# driver.net
KiCad netlist of a schematic drawn in EAGLE
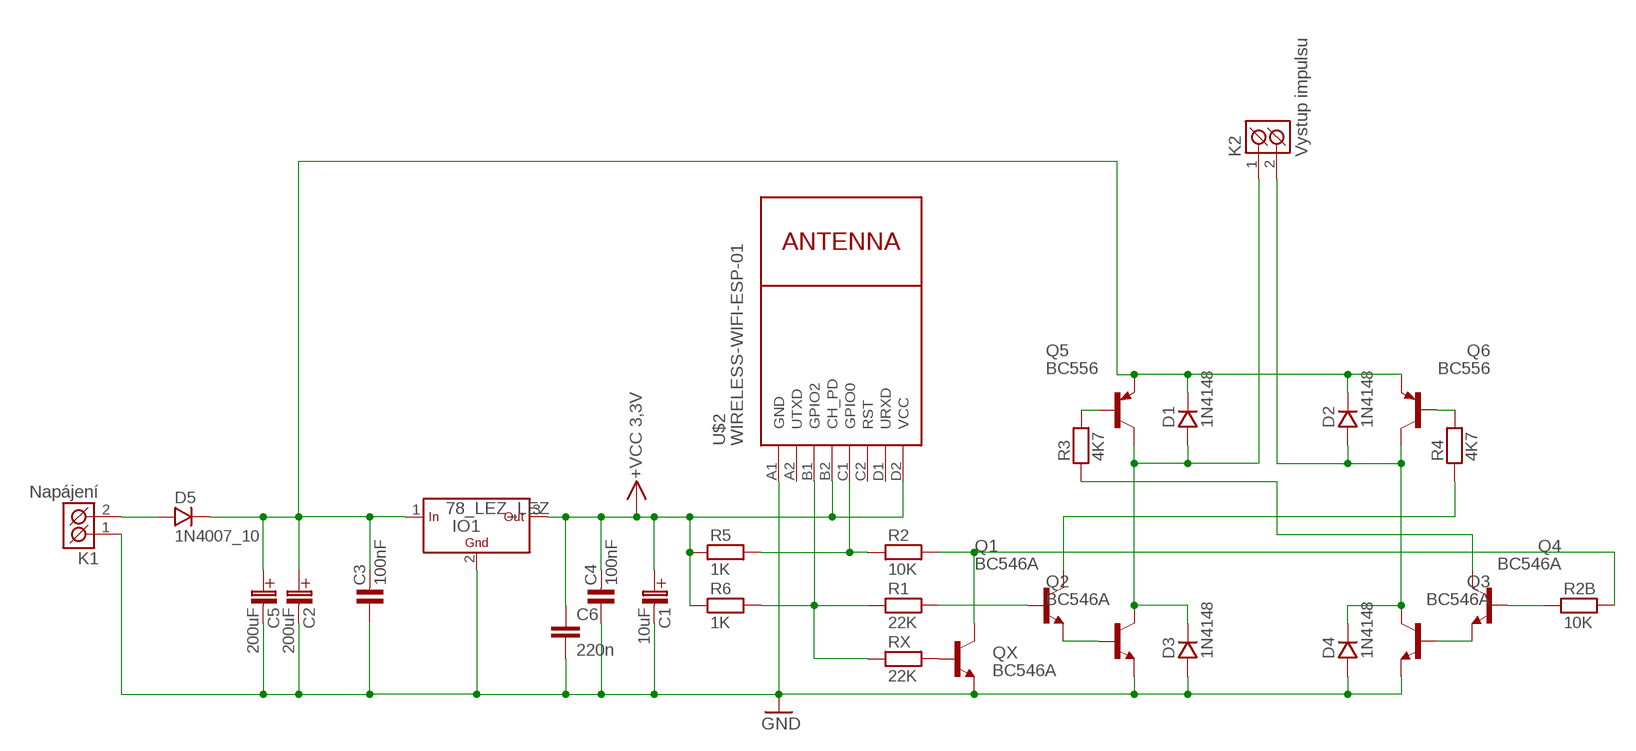
[diagram p0: schematic, sheet 1]

(export (version "E")
  (design (tool "Eeschema 10.0.6"))
  (components
    (comp (ref "C1")
      (value "10uF")
      (footprint "eagle-import:C-EL_2,5")
      (libsource (lib "eagle-import") (part "C-ELEKTROLYT_2,5"))
    )
    (comp (ref "C2")
      (value "200uF")
      (footprint "eagle-import:C-EL_5")
      (libsource (lib "eagle-import") (part "C-ELEKTROLYT_5"))
    )
    (comp (ref "C3")
      (value "100nF")
      (footprint "eagle-import:C-5")
      (libsource (lib "eagle-import") (part "C-KERAMIK_5"))
    )
    (comp (ref "C4")
      (value "100nF")
      (footprint "eagle-import:C-5")
      (libsource (lib "eagle-import") (part "C-KERAMIK_5"))
    )
    (comp (ref "C5")
      (value "200uF")
      (footprint "eagle-import:C-EL_5")
      (libsource (lib "eagle-import") (part "C-ELEKTROLYT_5"))
    )
    (comp (ref "C6")
      (value "220n")
      (footprint "eagle-import:C1206")
      (libsource (lib "eagle-import") (part "C-EUC1206"))
    )
    (comp (ref "D1")
      (value "1N4148")
      (footprint "eagle-import:DO35")
      (libsource (lib "eagle-import") (part "1N4148_7,5"))
    )
    (comp (ref "D2")
      (value "1N4148")
      (footprint "eagle-import:DO35")
      (libsource (lib "eagle-import") (part "1N4148_7,5"))
    )
    (comp (ref "D3")
      (value "1N4148")
      (footprint "eagle-import:DO35")
      (libsource (lib "eagle-import") (part "1N4148_7,5"))
    )
    (comp (ref "D4")
      (value "1N4148")
      (footprint "eagle-import:DO35")
      (libsource (lib "eagle-import") (part "1N4148_7,5"))
    )
    (comp (ref "D5")
      (value "1N4007_10")
      (footprint "eagle-import:DO41")
      (libsource (lib "eagle-import") (part "1N4007_10"))
    )
    (comp (ref "IO1")
      (value "78_LEZ_LEZ")
      (footprint "eagle-import:TO-220")
      (libsource (lib "eagle-import") (part "78??_LEZ"))
    )
    (comp (ref "K1")
      (value "Napájení")
      (footprint "eagle-import:CZM_5_2")
      (libsource (lib "eagle-import") (part "CZM_5/2"))
    )
    (comp (ref "K2")
      (value "Vystup impulsu")
      (footprint "eagle-import:CZM_5_2")
      (libsource (lib "eagle-import") (part "CZM_5/2"))
    )
    (comp (ref "Q1")
      (value "BC546A")
      (footprint "eagle-import:TO92-EBC")
      (libsource (lib "eagle-import") (part "BC546A"))
    )
    (comp (ref "Q2")
      (value "BC546A")
      (footprint "eagle-import:TO92-EBC")
      (libsource (lib "eagle-import") (part "BC546A"))
    )
    (comp (ref "Q3")
      (value "BC546A")
      (footprint "eagle-import:TO92-EBC")
      (libsource (lib "eagle-import") (part "BC546A"))
    )
    (comp (ref "Q4")
      (value "BC546A")
      (footprint "eagle-import:TO92-EBC")
      (libsource (lib "eagle-import") (part "BC546A"))
    )
    (comp (ref "Q5")
      (value "BC556")
      (footprint "eagle-import:TO92-EBC")
      (libsource (lib "eagle-import") (part "BC556"))
    )
    (comp (ref "Q6")
      (value "BC556")
      (footprint "eagle-import:TO92-EBC")
      (libsource (lib "eagle-import") (part "BC556"))
    )
    (comp (ref "QX")
      (value "BC546A")
      (footprint "eagle-import:TO92-EBC")
      (libsource (lib "eagle-import") (part "BC546A"))
    )
    (comp (ref "R1")
      (value "22K")
      (footprint "eagle-import:R-10")
      (libsource (lib "eagle-import") (part "R_10"))
    )
    (comp (ref "R2")
      (value "10K")
      (footprint "eagle-import:R-10")
      (libsource (lib "eagle-import") (part "R_10"))
    )
    (comp (ref "R2B")
      (value "10K")
      (footprint "eagle-import:R-10")
      (libsource (lib "eagle-import") (part "R_10"))
    )
    (comp (ref "R3")
      (value "4K7")
      (footprint "eagle-import:R-10")
      (libsource (lib "eagle-import") (part "R_10"))
    )
    (comp (ref "R4")
      (value "4K7")
      (footprint "eagle-import:R-10")
      (libsource (lib "eagle-import") (part "R_10"))
    )
    (comp (ref "R5")
      (value "1K")
      (footprint "eagle-import:R-10")
      (libsource (lib "eagle-import") (part "R_10"))
    )
    (comp (ref "R6")
      (value "1K")
      (footprint "eagle-import:R-10")
      (libsource (lib "eagle-import") (part "R_10"))
    )
    (comp (ref "RX")
      (value "22K")
      (footprint "eagle-import:R-10")
      (libsource (lib "eagle-import") (part "R_10"))
    )
    (comp (ref "U$2")
      (value "WIRELESS-WIFI-ESP-01")
      (footprint "eagle-import:WIRELESS-WIFI-ESP-01")
      (libsource (lib "eagle-import") (part "WIRELESS-WIFI-ESP-01"))
    )
  )
  (nets
    (net (code "1") (name "+VCC 3,3V") (class "Default")
      (node (ref "C1") (pin "C+") (pinfunction "C_EL+_C+") (pintype "passive"))
      (node (ref "C4") (pin "2") (pinfunction "2_2") (pintype "passive"))
      (node (ref "C6") (pin "1") (pinfunction "1_1") (pintype "passive"))
      (node (ref "IO1") (pin "3") (pinfunction "OUT_3") (pintype "passive"))
      (node (ref "R5") (pin "1") (pinfunction "1_1") (pintype "passive"))
      (node (ref "R6") (pin "1") (pinfunction "1_1") (pintype "passive"))
      (node (ref "U$2") (pin "B2") (pinfunction "CH_PD_B2") (pintype "bidirectional"))
      (node (ref "U$2") (pin "D2") (pinfunction "VCC_D2") (pintype "power_in"))
    )
    (net (code "2") (name "GND") (class "Default")
      (node (ref "C1") (pin "C-") (pinfunction "C_EL-_C-") (pintype "passive"))
      (node (ref "C2") (pin "C-") (pinfunction "C_EL-_C-") (pintype "passive"))
      (node (ref "C3") (pin "1") (pinfunction "1_1") (pintype "passive"))
      (node (ref "C4") (pin "1") (pinfunction "1_1") (pintype "passive"))
      (node (ref "C5") (pin "C-") (pinfunction "C_EL-_C-") (pintype "passive"))
      (node (ref "C6") (pin "2") (pinfunction "2_2") (pintype "passive"))
      (node (ref "D3") (pin "A") (pinfunction "A_A") (pintype "passive"))
      (node (ref "D4") (pin "A") (pinfunction "A_A") (pintype "passive"))
      (node (ref "IO1") (pin "2") (pinfunction "GND_2") (pintype "passive"))
      (node (ref "K1") (pin "1") (pinfunction "K1_1") (pintype "passive"))
      (node (ref "Q2") (pin "E") (pinfunction "E_E") (pintype "passive"))
      (node (ref "Q3") (pin "E") (pinfunction "E_E") (pintype "passive"))
      (node (ref "QX") (pin "E") (pinfunction "E_E") (pintype "passive"))
      (node (ref "U$2") (pin "A1") (pinfunction "GND_A1") (pintype "power_in"))
    )
    (net (code "3") (name "Net-(C2-C_EL+)") (class "Default")
      (node (ref "C2") (pin "C+") (pinfunction "C_EL+_C+") (pintype "passive"))
      (node (ref "C3") (pin "2") (pinfunction "2_2") (pintype "passive"))
      (node (ref "C5") (pin "C+") (pinfunction "C_EL+_C+") (pintype "passive"))
      (node (ref "D1") (pin "K") (pinfunction "K_K") (pintype "passive"))
      (node (ref "D2") (pin "K") (pinfunction "K_K") (pintype "passive"))
      (node (ref "D5") (pin "K") (pinfunction "K_K") (pintype "passive"))
      (node (ref "IO1") (pin "1") (pinfunction "IN_1") (pintype "passive"))
      (node (ref "Q5") (pin "E") (pinfunction "E_E") (pintype "passive"))
      (node (ref "Q6") (pin "E") (pinfunction "E_E") (pintype "passive"))
    )
    (net (code "4") (name "Net-(K1-K2)") (class "Default")
      (node (ref "D5") (pin "A") (pinfunction "A_A") (pintype "passive"))
      (node (ref "K1") (pin "2") (pinfunction "K2_2") (pintype "passive"))
    )
    (net (code "5") (name "Net-(K2-K1)") (class "Default")
      (node (ref "D1") (pin "A") (pinfunction "A_A") (pintype "passive"))
      (node (ref "D3") (pin "K") (pinfunction "K_K") (pintype "passive"))
      (node (ref "K2") (pin "1") (pinfunction "K1_1") (pintype "passive"))
      (node (ref "Q2") (pin "C") (pinfunction "C_C") (pintype "passive"))
      (node (ref "Q5") (pin "C") (pinfunction "C_C") (pintype "passive"))
    )
    (net (code "6") (name "Net-(K2-K2)") (class "Default")
      (node (ref "D2") (pin "A") (pinfunction "A_A") (pintype "passive"))
      (node (ref "D4") (pin "K") (pinfunction "K_K") (pintype "passive"))
      (node (ref "K2") (pin "2") (pinfunction "K2_2") (pintype "passive"))
      (node (ref "Q3") (pin "C") (pinfunction "C_C") (pintype "passive"))
      (node (ref "Q6") (pin "C") (pinfunction "C_C") (pintype "passive"))
    )
    (net (code "7") (name "Net-(Q1-PadB)") (class "Default")
      (node (ref "Q1") (pin "B") (pinfunction "B_B") (pintype "passive"))
      (node (ref "R1") (pin "2") (pinfunction "2_2") (pintype "passive"))
    )
    (net (code "8") (name "Net-(Q1-PadC)") (class "Default")
      (node (ref "Q1") (pin "C") (pinfunction "C_C") (pintype "passive"))
      (node (ref "R4") (pin "1") (pinfunction "1_1") (pintype "passive"))
    )
    (net (code "9") (name "Net-(Q1-PadE)") (class "Default")
      (node (ref "Q1") (pin "E") (pinfunction "E_E") (pintype "passive"))
      (node (ref "Q2") (pin "B") (pinfunction "B_B") (pintype "passive"))
    )
    (net (code "10") (name "Net-(Q3-PadB)") (class "Default")
      (node (ref "Q3") (pin "B") (pinfunction "B_B") (pintype "passive"))
      (node (ref "Q4") (pin "E") (pinfunction "E_E") (pintype "passive"))
    )
    (net (code "11") (name "Net-(Q4-PadB)") (class "Default")
      (node (ref "Q4") (pin "B") (pinfunction "B_B") (pintype "passive"))
      (node (ref "R2B") (pin "1") (pinfunction "1_1") (pintype "passive"))
    )
    (net (code "12") (name "Net-(Q4-PadC)") (class "Default")
      (node (ref "Q4") (pin "C") (pinfunction "C_C") (pintype "passive"))
      (node (ref "R3") (pin "1") (pinfunction "1_1") (pintype "passive"))
    )
    (net (code "13") (name "Net-(Q5-PadB)") (class "Default")
      (node (ref "Q5") (pin "B") (pinfunction "B_B") (pintype "passive"))
      (node (ref "R3") (pin "2") (pinfunction "2_2") (pintype "passive"))
    )
    (net (code "14") (name "Net-(Q6-PadB)") (class "Default")
      (node (ref "Q6") (pin "B") (pinfunction "B_B") (pintype "passive"))
      (node (ref "R4") (pin "2") (pinfunction "2_2") (pintype "passive"))
    )
    (net (code "15") (name "Net-(QX-PadB)") (class "Default")
      (node (ref "QX") (pin "B") (pinfunction "B_B") (pintype "passive"))
      (node (ref "RX") (pin "2") (pinfunction "2_2") (pintype "passive"))
    )
    (net (code "16") (name "Net-(QX-PadC)") (class "Default")
      (node (ref "QX") (pin "C") (pinfunction "C_C") (pintype "passive"))
      (node (ref "R2") (pin "2") (pinfunction "2_2") (pintype "passive"))
      (node (ref "R2B") (pin "2") (pinfunction "2_2") (pintype "passive"))
    )
    (net (code "17") (name "Net-(U$2-GPIO0)") (class "Default")
      (node (ref "R2") (pin "1") (pinfunction "1_1") (pintype "passive"))
      (node (ref "R5") (pin "2") (pinfunction "2_2") (pintype "passive"))
      (node (ref "U$2") (pin "C1") (pinfunction "GPIO0_C1") (pintype "bidirectional"))
    )
    (net (code "18") (name "Net-(U$2-GPIO2)") (class "Default")
      (node (ref "R1") (pin "1") (pinfunction "1_1") (pintype "passive"))
      (node (ref "R6") (pin "2") (pinfunction "2_2") (pintype "passive"))
      (node (ref "RX") (pin "1") (pinfunction "1_1") (pintype "passive"))
      (node (ref "U$2") (pin "B1") (pinfunction "GPIO2_B1") (pintype "bidirectional"))
    )
    (net (code "19") (name "unconnected-(U$2-RST-PadC2)") (class "Default")
      (node (ref "U$2") (pin "C2") (pinfunction "RST_C2") (pintype "bidirectional"))
    )
    (net (code "20") (name "unconnected-(U$2-URXD-PadD1)") (class "Default")
      (node (ref "U$2") (pin "D1") (pinfunction "URXD_D1") (pintype "bidirectional"))
    )
    (net (code "21") (name "unconnected-(U$2-UTXD-PadA2)") (class "Default")
      (node (ref "U$2") (pin "A2") (pinfunction "UTXD_A2") (pintype "bidirectional"))
    )
  )
)
